# guitar_tuner.net
KiCad netlist of a schematic drawn in EAGLE
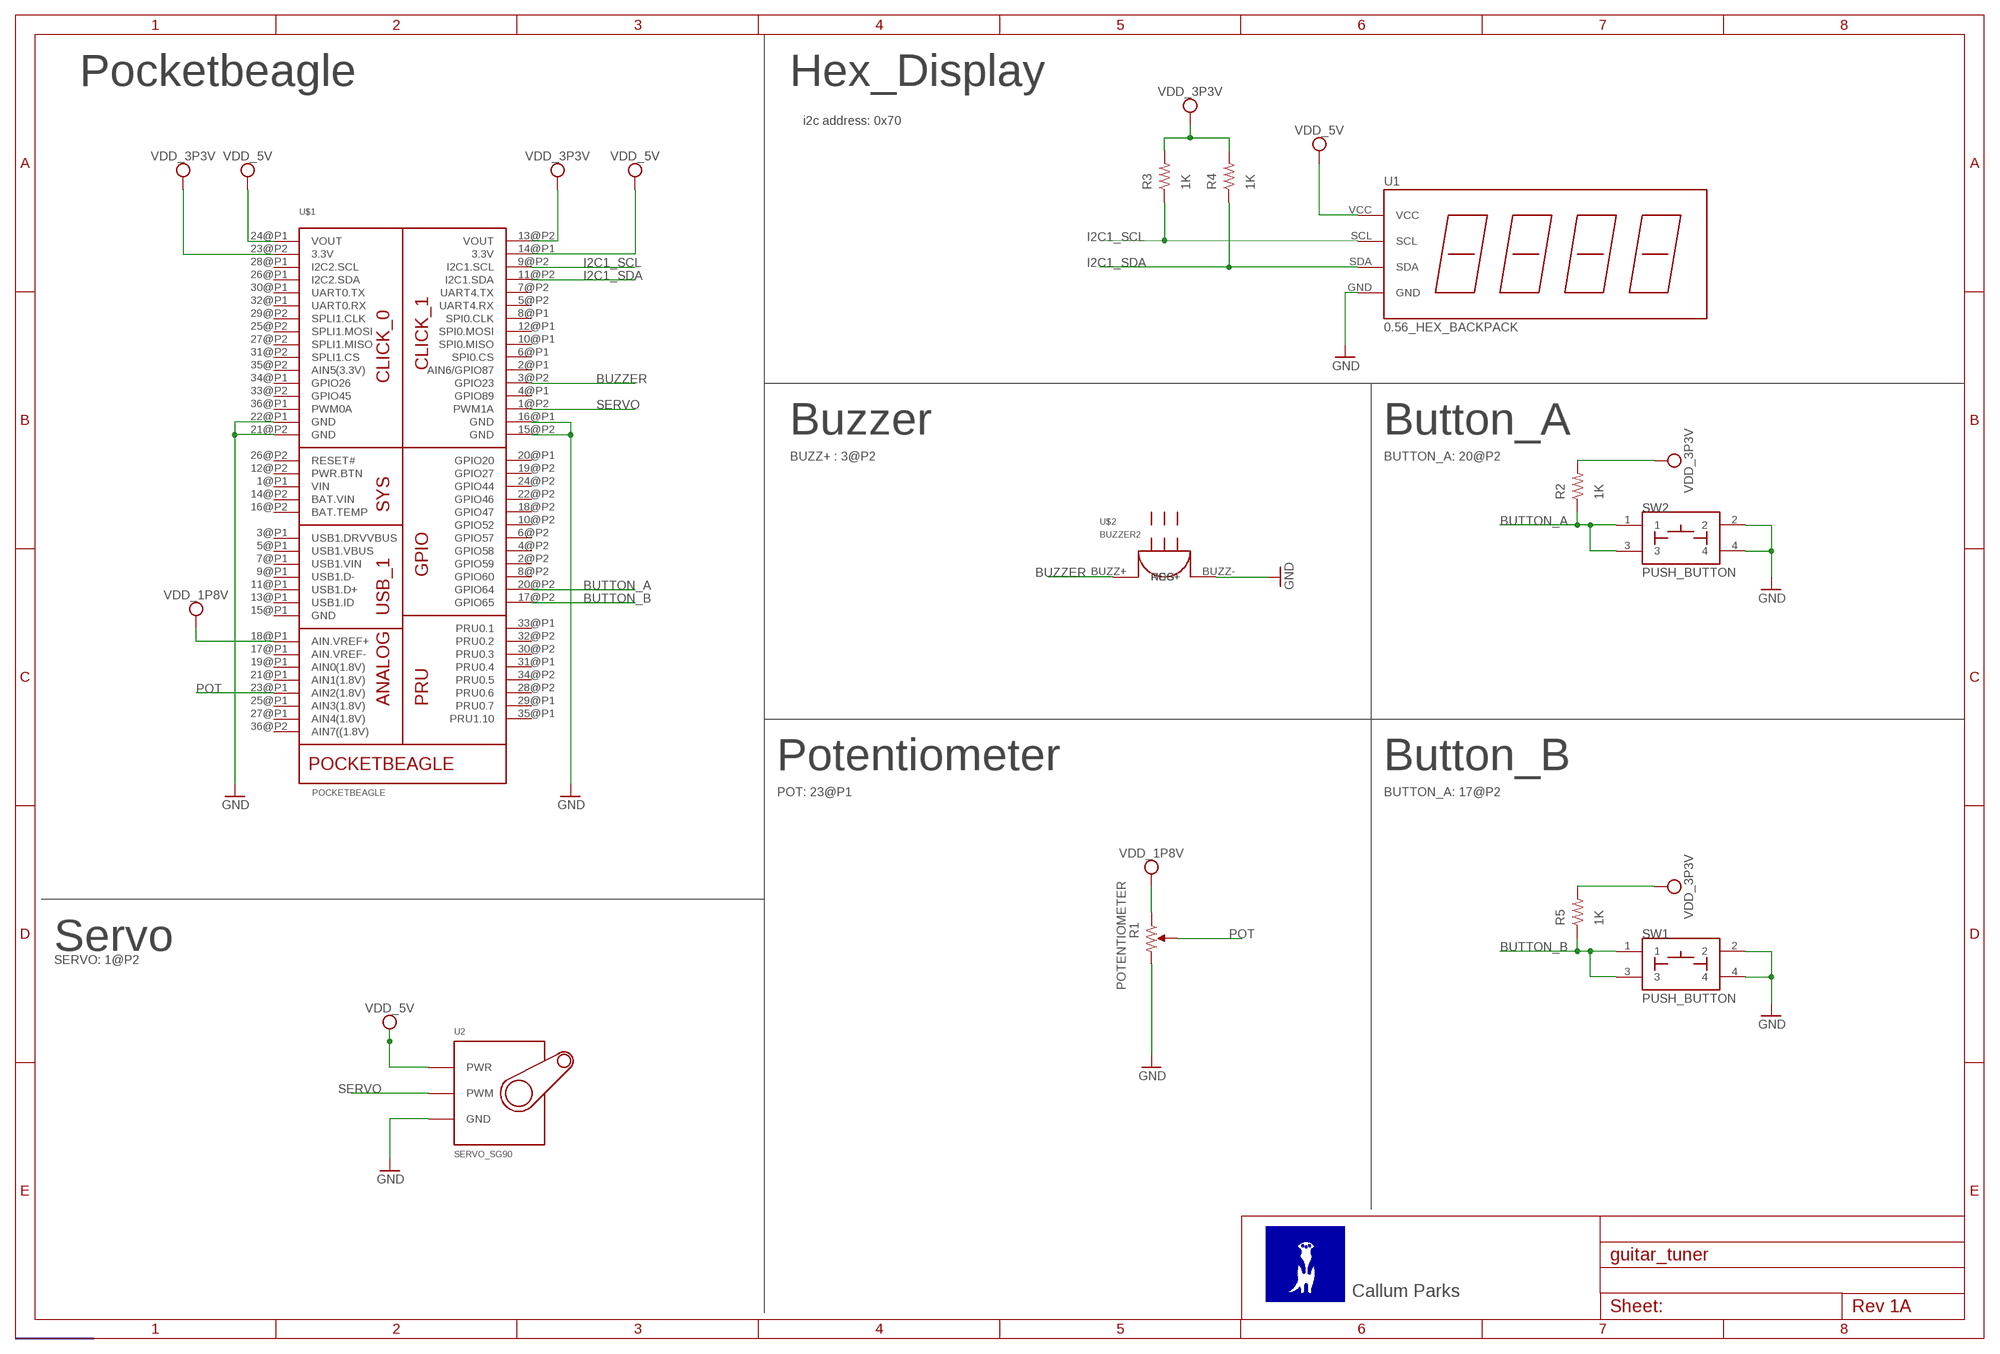
[diagram p0: schematic, sheet 1]

(export (version "E")
  (design (tool "Eeschema 10.0.6"))
  (components
    (comp (ref "R1")
      (value "POTENTIOMETER")
      (footprint "eagle-import:POT-PO90S")
      (libsource (lib "eagle-import") (part "POTENTIOMETER"))
    )
    (comp (ref "R2")
      (value "1K")
      (footprint "eagle-import:R0402")
      (libsource (lib "eagle-import") (part "R_R0402"))
    )
    (comp (ref "R3")
      (value "1K")
      (footprint "eagle-import:R0402")
      (libsource (lib "eagle-import") (part "R_R0402"))
    )
    (comp (ref "R4")
      (value "1K")
      (footprint "eagle-import:R0402")
      (libsource (lib "eagle-import") (part "R_R0402"))
    )
    (comp (ref "R5")
      (value "1K")
      (footprint "eagle-import:R0402")
      (libsource (lib "eagle-import") (part "R_R0402"))
    )
    (comp (ref "SW1")
      (value "PUSH_BUTTON")
      (footprint "eagle-import:BUTTON_12.5MM")
      (libsource (lib "eagle-import") (part "PUSH_BUTTON"))
    )
    (comp (ref "SW2")
      (value "PUSH_BUTTON")
      (footprint "eagle-import:BUTTON_12.5MM")
      (libsource (lib "eagle-import") (part "PUSH_BUTTON"))
    )
    (comp (ref "U$1")
      (value "POCKETBEAGLE")
      (footprint "eagle-import:POCKETBEAGLE")
      (libsource (lib "eagle-import") (part "POCKETBEAGLE"))
    )
    (comp (ref "U$2")
      (value "BUZZER2")
      (footprint "eagle-import:BUZZER2")
      (libsource (lib "eagle-import") (part "BUZZER2"))
    )
    (comp (ref "U1")
      (value "0.56_HEX_BACKPACK")
      (footprint "eagle-import:0.56_HEX_BACKPACK")
      (libsource (lib "eagle-import") (part "0.56_HEX_BACKPACK"))
    )
    (comp (ref "U2")
      (value "SERVO_SG90")
      (footprint "eagle-import:SERVO-X1")
      (libsource (lib "eagle-import") (part "SERVO_SG90"))
    )
  )
  (nets
    (net (code "1") (name "/BUTTON_A") (class "Default")
      (node (ref "R2") (pin "1") (pinfunction "1_1") (pintype "passive"))
      (node (ref "SW2") (pin "1") (pinfunction "1_1") (pintype "bidirectional"))
      (node (ref "SW2") (pin "3") (pinfunction "3_3") (pintype "bidirectional"))
      (node (ref "U$1") (pin "20@P2") (pinfunction "GPIO64_20@P2") (pintype "bidirectional"))
    )
    (net (code "2") (name "/BUTTON_B") (class "Default")
      (node (ref "R5") (pin "1") (pinfunction "1_1") (pintype "passive"))
      (node (ref "SW1") (pin "1") (pinfunction "1_1") (pintype "bidirectional"))
      (node (ref "SW1") (pin "3") (pinfunction "3_3") (pintype "bidirectional"))
      (node (ref "U$1") (pin "17@P2") (pinfunction "GPIO65_17@P2") (pintype "bidirectional"))
    )
    (net (code "3") (name "/BUZZER") (class "Default")
      (node (ref "U$1") (pin "3@P2") (pinfunction "GPIO23_3@P2") (pintype "bidirectional"))
      (node (ref "U$2") (pin "BUZZ+") (pinfunction "POS+_BUZZ+") (pintype "passive"))
    )
    (net (code "4") (name "/I2C1_SCL") (class "Default")
      (node (ref "U$1") (pin "9@P2") (pinfunction "I2C1.SCL_9@P2") (pintype "bidirectional"))
      (node (ref "U1") (pin "SCL") (pinfunction "SCL_SCL") (pintype "bidirectional"))
    )
    (net (code "5") (name "/I2C1_SDA") (class "Default")
      (node (ref "R4") (pin "1") (pinfunction "1_1") (pintype "passive"))
      (node (ref "U$1") (pin "11@P2") (pinfunction "I2C1.SDA_11@P2") (pintype "bidirectional"))
      (node (ref "U1") (pin "SDA") (pinfunction "SDA_SDA") (pintype "bidirectional"))
    )
    (net (code "6") (name "/POT") (class "Default")
      (node (ref "R1") (pin "S") (pinfunction "S_S") (pintype "bidirectional"))
      (node (ref "U$1") (pin "23@P1") (pinfunction "AIN2(1.8V)_23@P1") (pintype "bidirectional"))
    )
    (net (code "7") (name "/SERVO") (class "Default")
      (node (ref "U$1") (pin "1@P2") (pinfunction "PWM1A_1@P2") (pintype "bidirectional"))
      (node (ref "U2") (pin "SIG") (pinfunction "PWM_SIG") (pintype "bidirectional"))
    )
    (net (code "8") (name "GND") (class "Default")
      (node (ref "R1") (pin "CW") (pinfunction "CW_CW") (pintype "passive"))
      (node (ref "SW1") (pin "2") (pinfunction "2_2") (pintype "bidirectional"))
      (node (ref "SW1") (pin "4") (pinfunction "4_4") (pintype "bidirectional"))
      (node (ref "SW2") (pin "2") (pinfunction "2_2") (pintype "bidirectional"))
      (node (ref "SW2") (pin "4") (pinfunction "4_4") (pintype "bidirectional"))
      (node (ref "U$1") (pin "15@P2") (pinfunction "GND_15@P2") (pintype "bidirectional"))
      (node (ref "U$1") (pin "16@P1") (pinfunction "GND_16@P1") (pintype "bidirectional"))
      (node (ref "U$1") (pin "21@P2") (pinfunction "GND_21@P2") (pintype "bidirectional"))
      (node (ref "U$1") (pin "22@P1") (pinfunction "GND_22@P1") (pintype "bidirectional"))
      (node (ref "U$2") (pin "BUZZ-") (pinfunction "NEG-_BUZZ-") (pintype "passive"))
      (node (ref "U1") (pin "GND") (pinfunction "GND_GND") (pintype "bidirectional"))
      (node (ref "U2") (pin "GND") (pinfunction "GND_GND") (pintype "bidirectional"))
    )
    (net (code "9") (name "VDD_1P8V") (class "Default")
      (node (ref "R1") (pin "CCW") (pinfunction "CCW_CCW") (pintype "passive"))
      (node (ref "R2") (pin "2") (pinfunction "2_2") (pintype "passive"))
      (node (ref "R3") (pin "2") (pinfunction "2_2") (pintype "passive"))
      (node (ref "R4") (pin "2") (pinfunction "2_2") (pintype "passive"))
      (node (ref "R5") (pin "2") (pinfunction "2_2") (pintype "passive"))
      (node (ref "U$1") (pin "13@P2") (pinfunction "VOUT_13@P2") (pintype "bidirectional"))
      (node (ref "U$1") (pin "18@P1") (pinfunction "AIN.VREF+_18@P1") (pintype "bidirectional"))
      (node (ref "U$1") (pin "23@P2") (pinfunction "3.3V_23@P2") (pintype "bidirectional"))
    )
    (net (code "10") (name "VDD_5V") (class "Default")
      (node (ref "U$1") (pin "14@P1") (pinfunction "3.3V_14@P1") (pintype "bidirectional"))
      (node (ref "U$1") (pin "24@P1") (pinfunction "VOUT_24@P1") (pintype "bidirectional"))
      (node (ref "U1") (pin "VCC") (pinfunction "VCC_VCC") (pintype "power_in"))
      (node (ref "U2") (pin "PWR") (pinfunction "PWR_PWR") (pintype "bidirectional"))
    )
    (net (code "11") (name "unconnected-(R3-Pad1)") (class "Default")
      (node (ref "R3") (pin "1") (pinfunction "1_1") (pintype "passive"))
    )
    (net (code "12") (name "unconnected-(U$1-AIN.VREF--Pad17@P1)") (class "Default")
      (node (ref "U$1") (pin "17@P1") (pinfunction "AIN.VREF-_17@P1") (pintype "bidirectional"))
    )
    (net (code "13") (name "unconnected-(U$1-AIN0(1.8V)-Pad19@P1)") (class "Default")
      (node (ref "U$1") (pin "19@P1") (pinfunction "AIN0(1.8V)_19@P1") (pintype "bidirectional"))
    )
    (net (code "14") (name "unconnected-(U$1-AIN1(1.8V)-Pad21@P1)") (class "Default")
      (node (ref "U$1") (pin "21@P1") (pinfunction "AIN1(1.8V)_21@P1") (pintype "bidirectional"))
    )
    (net (code "15") (name "unconnected-(U$1-AIN3(1.8V)-Pad25@P1)") (class "Default")
      (node (ref "U$1") (pin "25@P1") (pinfunction "AIN3(1.8V)_25@P1") (pintype "bidirectional"))
    )
    (net (code "16") (name "unconnected-(U$1-AIN4(1.8V)-Pad27@P1)") (class "Default")
      (node (ref "U$1") (pin "27@P1") (pinfunction "AIN4(1.8V)_27@P1") (pintype "bidirectional"))
    )
    (net (code "17") (name "unconnected-(U$1-AIN5(3.3V)-Pad35@P2)") (class "Default")
      (node (ref "U$1") (pin "35@P2") (pinfunction "AIN5(3.3V)_35@P2") (pintype "bidirectional"))
    )
    (net (code "18") (name "unconnected-(U$1-AIN6{slash}GPIO87-Pad2@P1)") (class "Default")
      (node (ref "U$1") (pin "2@P1") (pinfunction "AIN6/GPIO87_2@P1") (pintype "bidirectional"))
    )
    (net (code "19") (name "unconnected-(U$1-AIN7((1.8V)-Pad36@P2)") (class "Default")
      (node (ref "U$1") (pin "36@P2") (pinfunction "AIN7((1.8V)_36@P2") (pintype "bidirectional"))
    )
    (net (code "20") (name "unconnected-(U$1-BAT.TEMP-Pad16@P2)") (class "Default")
      (node (ref "U$1") (pin "16@P2") (pinfunction "BAT.TEMP_16@P2") (pintype "bidirectional"))
    )
    (net (code "21") (name "unconnected-(U$1-BAT.VIN-Pad14@P2)") (class "Default")
      (node (ref "U$1") (pin "14@P2") (pinfunction "BAT.VIN_14@P2") (pintype "bidirectional"))
    )
    (net (code "22") (name "unconnected-(U$1-GND-Pad15@P1)") (class "Default")
      (node (ref "U$1") (pin "15@P1") (pinfunction "GND_15@P1") (pintype "bidirectional"))
    )
    (net (code "23") (name "unconnected-(U$1-GPIO20-Pad20@P1)") (class "Default")
      (node (ref "U$1") (pin "20@P1") (pinfunction "GPIO20_20@P1") (pintype "bidirectional"))
    )
    (net (code "24") (name "unconnected-(U$1-GPIO26-Pad34@P1)") (class "Default")
      (node (ref "U$1") (pin "34@P1") (pinfunction "GPIO26_34@P1") (pintype "bidirectional"))
    )
    (net (code "25") (name "unconnected-(U$1-GPIO27-Pad19@P2)") (class "Default")
      (node (ref "U$1") (pin "19@P2") (pinfunction "GPIO27_19@P2") (pintype "bidirectional"))
    )
    (net (code "26") (name "unconnected-(U$1-GPIO44-Pad24@P2)") (class "Default")
      (node (ref "U$1") (pin "24@P2") (pinfunction "GPIO44_24@P2") (pintype "bidirectional"))
    )
    (net (code "27") (name "unconnected-(U$1-GPIO45-Pad33@P2)") (class "Default")
      (node (ref "U$1") (pin "33@P2") (pinfunction "GPIO45_33@P2") (pintype "bidirectional"))
    )
    (net (code "28") (name "unconnected-(U$1-GPIO46-Pad22@P2)") (class "Default")
      (node (ref "U$1") (pin "22@P2") (pinfunction "GPIO46_22@P2") (pintype "bidirectional"))
    )
    (net (code "29") (name "unconnected-(U$1-GPIO47-Pad18@P2)") (class "Default")
      (node (ref "U$1") (pin "18@P2") (pinfunction "GPIO47_18@P2") (pintype "bidirectional"))
    )
    (net (code "30") (name "unconnected-(U$1-GPIO52-Pad10@P2)") (class "Default")
      (node (ref "U$1") (pin "10@P2") (pinfunction "GPIO52_10@P2") (pintype "bidirectional"))
    )
    (net (code "31") (name "unconnected-(U$1-GPIO57-Pad6@P2)") (class "Default")
      (node (ref "U$1") (pin "6@P2") (pinfunction "GPIO57_6@P2") (pintype "bidirectional"))
    )
    (net (code "32") (name "unconnected-(U$1-GPIO58-Pad4@P2)") (class "Default")
      (node (ref "U$1") (pin "4@P2") (pinfunction "GPIO58_4@P2") (pintype "bidirectional"))
    )
    (net (code "33") (name "unconnected-(U$1-GPIO59-Pad2@P2)") (class "Default")
      (node (ref "U$1") (pin "2@P2") (pinfunction "GPIO59_2@P2") (pintype "bidirectional"))
    )
    (net (code "34") (name "unconnected-(U$1-GPIO60-Pad8@P2)") (class "Default")
      (node (ref "U$1") (pin "8@P2") (pinfunction "GPIO60_8@P2") (pintype "bidirectional"))
    )
    (net (code "35") (name "unconnected-(U$1-GPIO89-Pad4@P1)") (class "Default")
      (node (ref "U$1") (pin "4@P1") (pinfunction "GPIO89_4@P1") (pintype "bidirectional"))
    )
    (net (code "36") (name "unconnected-(U$1-I2C2.SCL-Pad28@P1)") (class "Default")
      (node (ref "U$1") (pin "28@P1") (pinfunction "I2C2.SCL_28@P1") (pintype "bidirectional"))
    )
    (net (code "37") (name "unconnected-(U$1-I2C2.SDA-Pad26@P1)") (class "Default")
      (node (ref "U$1") (pin "26@P1") (pinfunction "I2C2.SDA_26@P1") (pintype "bidirectional"))
    )
    (net (code "38") (name "unconnected-(U$1-PRU0.1-Pad33@P1)") (class "Default")
      (node (ref "U$1") (pin "33@P1") (pinfunction "PRU0.1_33@P1") (pintype "bidirectional"))
    )
    (net (code "39") (name "unconnected-(U$1-PRU0.2-Pad32@P2)") (class "Default")
      (node (ref "U$1") (pin "32@P2") (pinfunction "PRU0.2_32@P2") (pintype "bidirectional"))
    )
    (net (code "40") (name "unconnected-(U$1-PRU0.3-Pad30@P2)") (class "Default")
      (node (ref "U$1") (pin "30@P2") (pinfunction "PRU0.3_30@P2") (pintype "bidirectional"))
    )
    (net (code "41") (name "unconnected-(U$1-PRU0.4-Pad31@P1)") (class "Default")
      (node (ref "U$1") (pin "31@P1") (pinfunction "PRU0.4_31@P1") (pintype "bidirectional"))
    )
    (net (code "42") (name "unconnected-(U$1-PRU0.5-Pad34@P2)") (class "Default")
      (node (ref "U$1") (pin "34@P2") (pinfunction "PRU0.5_34@P2") (pintype "bidirectional"))
    )
    (net (code "43") (name "unconnected-(U$1-PRU0.6-Pad28@P2)") (class "Default")
      (node (ref "U$1") (pin "28@P2") (pinfunction "PRU0.6_28@P2") (pintype "bidirectional"))
    )
    (net (code "44") (name "unconnected-(U$1-PRU0.7-Pad29@P1)") (class "Default")
      (node (ref "U$1") (pin "29@P1") (pinfunction "PRU0.7_29@P1") (pintype "bidirectional"))
    )
    (net (code "45") (name "unconnected-(U$1-PRU1.10-Pad35@P1)") (class "Default")
      (node (ref "U$1") (pin "35@P1") (pinfunction "PRU1.10_35@P1") (pintype "bidirectional"))
    )
    (net (code "46") (name "unconnected-(U$1-PWM0A-Pad36@P1)") (class "Default")
      (node (ref "U$1") (pin "36@P1") (pinfunction "PWM0A_36@P1") (pintype "bidirectional"))
    )
    (net (code "47") (name "unconnected-(U$1-PWR.BTN-Pad12@P2)") (class "Default")
      (node (ref "U$1") (pin "12@P2") (pinfunction "PWR.BTN_12@P2") (pintype "bidirectional"))
    )
    (net (code "48") (name "unconnected-(U$1-RESET#-Pad26@P2)") (class "Default")
      (node (ref "U$1") (pin "26@P2") (pinfunction "RESET#_26@P2") (pintype "bidirectional"))
    )
    (net (code "49") (name "unconnected-(U$1-SPI0.CLK-Pad8@P1)") (class "Default")
      (node (ref "U$1") (pin "8@P1") (pinfunction "SPI0.CLK_8@P1") (pintype "bidirectional"))
    )
    (net (code "50") (name "unconnected-(U$1-SPI0.CS-Pad6@P1)") (class "Default")
      (node (ref "U$1") (pin "6@P1") (pinfunction "SPI0.CS_6@P1") (pintype "bidirectional"))
    )
    (net (code "51") (name "unconnected-(U$1-SPI0.MISO-Pad10@P1)") (class "Default")
      (node (ref "U$1") (pin "10@P1") (pinfunction "SPI0.MISO_10@P1") (pintype "bidirectional"))
    )
    (net (code "52") (name "unconnected-(U$1-SPI0.MOSI-Pad12@P1)") (class "Default")
      (node (ref "U$1") (pin "12@P1") (pinfunction "SPI0.MOSI_12@P1") (pintype "bidirectional"))
    )
    (net (code "53") (name "unconnected-(U$1-SPLI1.CLK-Pad29@P2)") (class "Default")
      (node (ref "U$1") (pin "29@P2") (pinfunction "SPLI1.CLK_29@P2") (pintype "bidirectional"))
    )
    (net (code "54") (name "unconnected-(U$1-SPLI1.CS-Pad31@P2)") (class "Default")
      (node (ref "U$1") (pin "31@P2") (pinfunction "SPLI1.CS_31@P2") (pintype "bidirectional"))
    )
    (net (code "55") (name "unconnected-(U$1-SPLI1.MISO-Pad27@P2)") (class "Default")
      (node (ref "U$1") (pin "27@P2") (pinfunction "SPLI1.MISO_27@P2") (pintype "bidirectional"))
    )
    (net (code "56") (name "unconnected-(U$1-SPLI1.MOSI-Pad25@P2)") (class "Default")
      (node (ref "U$1") (pin "25@P2") (pinfunction "SPLI1.MOSI_25@P2") (pintype "bidirectional"))
    )
    (net (code "57") (name "unconnected-(U$1-UART0.RX-Pad32@P1)") (class "Default")
      (node (ref "U$1") (pin "32@P1") (pinfunction "UART0.RX_32@P1") (pintype "bidirectional"))
    )
    (net (code "58") (name "unconnected-(U$1-UART0.TX-Pad30@P1)") (class "Default")
      (node (ref "U$1") (pin "30@P1") (pinfunction "UART0.TX_30@P1") (pintype "bidirectional"))
    )
    (net (code "59") (name "unconnected-(U$1-UART4.RX-Pad5@P2)") (class "Default")
      (node (ref "U$1") (pin "5@P2") (pinfunction "UART4.RX_5@P2") (pintype "bidirectional"))
    )
    (net (code "60") (name "unconnected-(U$1-UART4.TX-Pad7@P2)") (class "Default")
      (node (ref "U$1") (pin "7@P2") (pinfunction "UART4.TX_7@P2") (pintype "bidirectional"))
    )
    (net (code "61") (name "unconnected-(U$1-USB1.D+-Pad11@P1)") (class "Default")
      (node (ref "U$1") (pin "11@P1") (pinfunction "USB1.D+_11@P1") (pintype "bidirectional"))
    )
    (net (code "62") (name "unconnected-(U$1-USB1.D--Pad9@P1)") (class "Default")
      (node (ref "U$1") (pin "9@P1") (pinfunction "USB1.D-_9@P1") (pintype "bidirectional"))
    )
    (net (code "63") (name "unconnected-(U$1-USB1.DRVVBUS-Pad3@P1)") (class "Default")
      (node (ref "U$1") (pin "3@P1") (pinfunction "USB1.DRVVBUS_3@P1") (pintype "bidirectional"))
    )
    (net (code "64") (name "unconnected-(U$1-USB1.ID-Pad13@P1)") (class "Default")
      (node (ref "U$1") (pin "13@P1") (pinfunction "USB1.ID_13@P1") (pintype "bidirectional"))
    )
    (net (code "65") (name "unconnected-(U$1-USB1.VBUS-Pad5@P1)") (class "Default")
      (node (ref "U$1") (pin "5@P1") (pinfunction "USB1.VBUS_5@P1") (pintype "bidirectional"))
    )
    (net (code "66") (name "unconnected-(U$1-USB1.VIN-Pad7@P1)") (class "Default")
      (node (ref "U$1") (pin "7@P1") (pinfunction "USB1.VIN_7@P1") (pintype "bidirectional"))
    )
    (net (code "67") (name "unconnected-(U$1-VIN-Pad1@P1)") (class "Default")
      (node (ref "U$1") (pin "1@P1") (pinfunction "VIN_1@P1") (pintype "bidirectional"))
    )
  )
)
